# radioslave_v3.net
KiCad netlist of a schematic drawn in Altium Designer
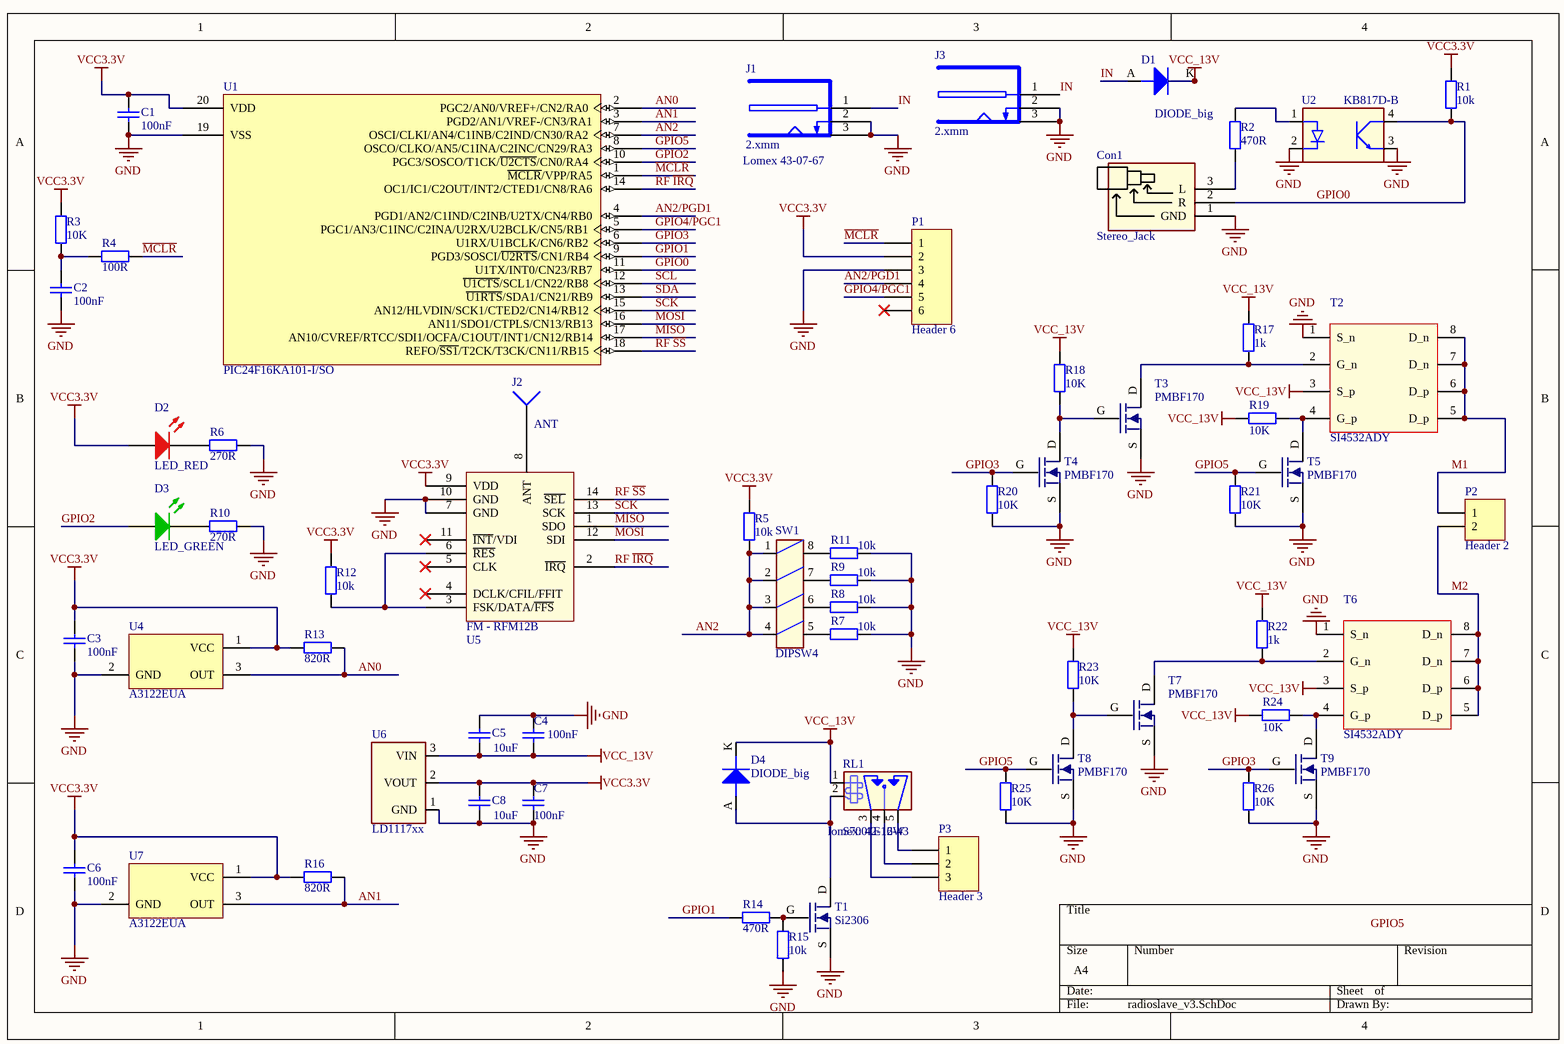
[diagram p0: radioslave_v3.SchDoc]

(export (version "E")
  (design (tool "Eeschema 10.0.6"))
  (components
    (comp (ref "C1")
      (value "100nF")
      (footprint "FP_0805_CAP_060")
      (description "Capacitor")
      (fields (field (name "PUBLISHER") "Altium Limited"))
      (libsource (lib "Miscellaneous Devices") (part "Cap"))
    )
    (comp (ref "C2")
      (value "100nF")
      (footprint "FP_0805_CAP_060")
      (description "Capacitor")
      (fields (field (name "PUBLISHER") "Altium Limited"))
      (libsource (lib "Miscellaneous Devices") (part "Cap"))
    )
    (comp (ref "C3")
      (value "100nF")
      (footprint "FP_0805_CAP_060")
      (description "Capacitor")
      (fields (field (name "PUBLISHER") "Altium Limited"))
      (libsource (lib "Miscellaneous Devices") (part "Cap"))
    )
    (comp (ref "C4")
      (value "100nF")
      (footprint "FP_0603_CAP_080")
      (description "Capacitor")
      (fields (field (name "PUBLISHER") "Altium Limited"))
      (libsource (lib "Miscellaneous Devices") (part "Cap"))
    )
    (comp (ref "C5")
      (value "10uF")
      (footprint "FP_1206_CAP_085")
      (description "Capacitor")
      (fields (field (name "PUBLISHER") "Altium Limited"))
      (libsource (lib "Miscellaneous Devices") (part "Cap"))
    )
    (comp (ref "C6")
      (value "100nF")
      (footprint "FP_0805_CAP_060")
      (description "Capacitor")
      (fields (field (name "PUBLISHER") "Altium Limited"))
      (libsource (lib "Miscellaneous Devices") (part "Cap"))
    )
    (comp (ref "C7")
      (value "100nF")
      (footprint "FP_0603_CAP_080")
      (description "Capacitor")
      (fields (field (name "PUBLISHER") "Altium Limited"))
      (libsource (lib "Miscellaneous Devices") (part "Cap"))
    )
    (comp (ref "C8")
      (value "10uF")
      (footprint "FP_1206_CAP_085")
      (description "Capacitor")
      (fields (field (name "PUBLISHER") "Altium Limited"))
      (libsource (lib "Miscellaneous Devices") (part "Cap"))
    )
    (comp (ref "Con1")
      (value "Stereo_Jack")
      (footprint "STEREO_JACK")
      (libsource (lib "Connector") (part "Stereo_Jack"))
    )
    (comp (ref "D1")
      (value "DIODE_big")
      (footprint "FP_SMA DO214AC")
      (libsource (lib "Diode") (part "DIODE_big"))
    )
    (comp (ref "D2")
      (value "LED_RED")
      (footprint "FP_0805_LED_RED")
      (description "Typical LED")
      (libsource (lib "Led_optical") (part "LED_R"))
    )
    (comp (ref "D3")
      (value "LED_GREEN")
      (footprint "FP_0805_LED_RED")
      (description "Typical LED")
      (libsource (lib "Led_optical") (part "LED_G"))
    )
    (comp (ref "D4")
      (value "DIODE_big")
      (footprint "FP_SMA DO214AC")
      (libsource (lib "Diode") (part "DIODE_big"))
    )
    (comp (ref "J1")
      (value "2.xmm")
      (footprint "FP_DC_TAP_ANYA")
      (description "2.xmm DC HEBA25 TÁPFESZÜLTSÉG ALJZAT ZÁRT, NYÁKBA 90°")
      (fields (field (name "ORDER INFO") "Lomex 43-07-67"))
      (libsource (lib "Connector") (part "DC_TAP_ANYA"))
    )
    (comp (ref "J2")
      (value "ANT")
      (footprint "PIN1")
      (description "Socket")
      (fields (field (name "PUBLISHER") "Altium Limited"))
      (libsource (lib "Miscellaneous Connectors") (part "Socket"))
    )
    (comp (ref "J3")
      (value "2.xmm")
      (footprint "FP_DC_TAP_ANYA")
      (description "2.xmm DC HEBA25 TÁPFESZÜLTSÉG ALJZAT ZÁRT, NYÁKBA 90°")
      (libsource (lib "Connector") (part "DC_TAP_ANYA"))
    )
    (comp (ref "P1")
      (value "Header 6")
      (footprint "HDR1X6")
      (description "Header, 6-Pin")
      (fields (field (name "PUBLISHER") "Altium Limited"))
      (libsource (lib "Miscellaneous Connectors") (part "Header 6"))
    )
    (comp (ref "P2")
      (value "Header 2")
      (footprint "HDR1X2")
      (description "Header, 2-Pin")
      (fields (field (name "PUBLISHER") "Altium Limited"))
      (libsource (lib "Miscellaneous Connectors") (part "Header 2"))
    )
    (comp (ref "P3")
      (value "Header 3")
      (footprint "SORKAPOCS 3 P RM3.81")
      (description "Header, 3-Pin")
      (fields (field (name "PUBLISHER") "Altium Limited"))
      (libsource (lib "Miscellaneous Connectors") (part "Header 3"))
    )
    (comp (ref "R1")
      (value "10k")
      (footprint "FP_0805_RES")
      (description "Resistor")
      (fields (field (name "PUBLISHER") "Altium Limited"))
      (libsource (lib "") (part "Res3_1"))
    )
    (comp (ref "R2")
      (value "470R")
      (footprint "FP_0805_RES")
      (description "Resistor")
      (fields (field (name "PUBLISHER") "Altium Limited"))
      (libsource (lib "") (part "Res3_1"))
    )
    (comp (ref "R3")
      (value "10K")
      (footprint "FP_0805_RES")
      (description "Resistor")
      (fields (field (name "PUBLISHER") "Altium Limited"))
      (libsource (lib "") (part "Res3_1"))
    )
    (comp (ref "R4")
      (value "100R")
      (footprint "FP_0805_RES")
      (description "Resistor")
      (fields (field (name "PUBLISHER") "Altium Limited"))
      (libsource (lib "Miscellaneous Devices") (part "Res3"))
    )
    (comp (ref "R5")
      (value "10k")
      (footprint "FP_0805_RES")
      (description "Resistor")
      (fields (field (name "PUBLISHER") "Altium Limited"))
      (libsource (lib "") (part "Res3_1"))
    )
    (comp (ref "R6")
      (value "270R")
      (footprint "FP_0805_RES")
      (description "Resistor")
      (fields (field (name "PUBLISHER") "Altium Limited"))
      (libsource (lib "Miscellaneous Devices") (part "Res3"))
    )
    (comp (ref "R7")
      (value "10k")
      (footprint "FP_0805_RES")
      (description "Resistor")
      (fields (field (name "PUBLISHER") "Altium Limited"))
      (libsource (lib "Miscellaneous Devices") (part "Res3"))
    )
    (comp (ref "R8")
      (value "10k")
      (footprint "FP_0805_RES")
      (description "Resistor")
      (fields (field (name "PUBLISHER") "Altium Limited"))
      (libsource (lib "Miscellaneous Devices") (part "Res3"))
    )
    (comp (ref "R9")
      (value "10k")
      (footprint "FP_0805_RES")
      (description "Resistor")
      (fields (field (name "PUBLISHER") "Altium Limited"))
      (libsource (lib "Miscellaneous Devices") (part "Res3"))
    )
    (comp (ref "R10")
      (value "270R")
      (footprint "FP_0805_RES")
      (description "Resistor")
      (fields (field (name "PUBLISHER") "Altium Limited"))
      (libsource (lib "Miscellaneous Devices") (part "Res3"))
    )
    (comp (ref "R11")
      (value "10k")
      (footprint "FP_0805_RES")
      (description "Resistor")
      (fields (field (name "PUBLISHER") "Altium Limited"))
      (libsource (lib "Miscellaneous Devices") (part "Res3"))
    )
    (comp (ref "R12")
      (value "10k")
      (footprint "FP_0805_RES")
      (description "Resistor")
      (fields (field (name "PUBLISHER") "Altium Limited"))
      (libsource (lib "") (part "Res3_2"))
    )
    (comp (ref "R13")
      (value "820R")
      (footprint "FP_0805_RES")
      (description "Resistor")
      (fields (field (name "PUBLISHER") "Altium Limited"))
      (libsource (lib "Miscellaneous Devices") (part "Res3"))
    )
    (comp (ref "R14")
      (value "470R")
      (footprint "FP_0805_RES")
      (description "Resistor")
      (fields (field (name "PUBLISHER") "Altium Limited"))
      (libsource (lib "Miscellaneous Devices") (part "Res3"))
    )
    (comp (ref "R15")
      (value "10k")
      (footprint "FP_0805_RES")
      (description "Resistor")
      (fields (field (name "PUBLISHER") "Altium Limited"))
      (libsource (lib "") (part "Res3_2"))
    )
    (comp (ref "R16")
      (value "820R")
      (footprint "FP_0805_RES")
      (description "Resistor")
      (fields (field (name "PUBLISHER") "Altium Limited"))
      (libsource (lib "Miscellaneous Devices") (part "Res3"))
    )
    (comp (ref "R17")
      (value "1k")
      (footprint "FP_0603_RES")
      (description "Resistor")
      (libsource (lib "") (part "Res3_1"))
    )
    (comp (ref "R18")
      (value "10K")
      (footprint "FP_0603_RES")
      (description "Resistor")
      (libsource (lib "") (part "RES_1"))
    )
    (comp (ref "R19")
      (value "10K")
      (footprint "FP_0603_RES")
      (description "Resistor")
      (libsource (lib "Resistor") (part "RES"))
    )
    (comp (ref "R20")
      (value "10K")
      (footprint "FP_0603_RES")
      (description "Resistor")
      (libsource (lib "") (part "RES_1"))
    )
    (comp (ref "R21")
      (value "10K")
      (footprint "FP_0603_RES")
      (description "Resistor")
      (libsource (lib "") (part "RES_1"))
    )
    (comp (ref "R22")
      (value "1k")
      (footprint "FP_0603_RES")
      (description "Resistor")
      (libsource (lib "") (part "Res3_1"))
    )
    (comp (ref "R23")
      (value "10K")
      (footprint "FP_0603_RES")
      (description "Resistor")
      (libsource (lib "") (part "RES_1"))
    )
    (comp (ref "R24")
      (value "10K")
      (footprint "FP_0603_RES")
      (description "Resistor")
      (libsource (lib "Resistor") (part "RES"))
    )
    (comp (ref "R25")
      (value "10K")
      (footprint "FP_0603_RES")
      (description "Resistor")
      (libsource (lib "") (part "RES_1"))
    )
    (comp (ref "R26")
      (value "10K")
      (footprint "FP_0603_RES")
      (description "Resistor")
      (libsource (lib "") (part "RES_1"))
    )
    (comp (ref "RL1")
      (value "S7001E12W")
      (footprint "RELAY_MORSE")
      (description "S7001E12W  12V morse 230AC/10A")
      (fields (field (name "ORDER INFO") "lomex: 42-16-43"))
      (libsource (lib "Switch") (part "RELAY_MORSE"))
    )
    (comp (ref "SW1")
      (value "DIPSW4")
      (footprint "DIP switch 4 TH")
      (libsource (lib "Switch") (part "DIPSW4"))
    )
    (comp (ref "T1") (value "Si2306") (footprint "FET_SOT23") (libsource (lib "FET") (part "NMOS")))
    (comp (ref "T2")
      (value "SI4532ADY")
      (footprint "FET_SOIC8_copper_pad")
      (libsource (lib "FET") (part "SI4532ADY   3.7A   30V"))
    )
    (comp (ref "T3") (value "PMBF170") (footprint "FET_SOT23") (libsource (lib "FET") (part "NMOS")))
    (comp (ref "T4") (value "PMBF170") (footprint "FET_SOT23") (libsource (lib "FET") (part "NMOS")))
    (comp (ref "T5") (value "PMBF170") (footprint "FET_SOT23") (libsource (lib "FET") (part "NMOS")))
    (comp (ref "T6")
      (value "SI4532ADY")
      (footprint "FET_SOIC8_copper_pad")
      (libsource (lib "FET") (part "SI4532ADY   3.7A   30V"))
    )
    (comp (ref "T7") (value "PMBF170") (footprint "FET_SOT23") (libsource (lib "FET") (part "NMOS")))
    (comp (ref "T8") (value "PMBF170") (footprint "FET_SOT23") (libsource (lib "FET") (part "NMOS")))
    (comp (ref "T9") (value "PMBF170") (footprint "FET_SOT23") (libsource (lib "FET") (part "NMOS")))
    (comp (ref "U1")
      (value "PIC24F16KA101-I/SO")
      (footprint "SOIC-SO20_N")
      (fields (field (name "PUBLISHER") "Altium Limited"))
      (libsource (lib "Microchip Microcontroller 16-Bit PIC24F") (part "PIC24F16KA101-I/SO"))
    )
    (comp (ref "U2")
      (value "KB817D-B")
      (footprint "SOP-4L")
      (description "KB817D-B (KIN) SOP-4L OPTOCOUPLER TRANS-OUT 300-600% 5kV SOP-4L [84-00-48]")
      (libsource (lib "Led_optical") (part "KB817D-B"))
    )
    (comp (ref "U4")
      (value "A3122EUA")
      (footprint "Allegro_hall sensor")
      (description "Hall-Effect Switch for High-Temperature Operation")
      (fields (field (name "PUBLISHER") "Altium Limited"))
      (libsource (lib "Sensor") (part "A3122EUA"))
    )
    (comp (ref "U5")
      (value "RFM12B")
      (footprint "RFM12B-S1")
      (description "FM Module")
      (libsource (lib "EtherIOv2") (part "RFM12B"))
    )
    (comp (ref "U6")
      (value "LD1117xx")
      (footprint "SUPPLY_SOT223")
      (description "LD1117xx 3,3V lin reg")
      (libsource (lib "Supply") (part "LD1117xx"))
    )
    (comp (ref "U7")
      (value "A3122EUA")
      (footprint "Allegro_hall sensor")
      (description "Hall-Effect Switch for High-Temperature Operation")
      (fields (field (name "PUBLISHER") "Altium Limited"))
      (libsource (lib "Sensor") (part "A3122EUA"))
    )
  )
  (nets
    (net (code "1") (name "/AN0") (class "Default")
      (node (ref "R13") (pin "1") (pinfunction "1_1") (pintype "passive"))
      (node (ref "U1") (pin "2") (pinfunction "PGC2/AN0/VREF+/CN2/RA0_2") (pintype "bidirectional"))
      (node (ref "U4") (pin "3") (pinfunction "OUT_3") (pintype "open_collector"))
    )
    (net (code "2") (name "/AN1") (class "Default")
      (node (ref "R16") (pin "1") (pinfunction "1_1") (pintype "passive"))
      (node (ref "U1") (pin "3") (pinfunction "PGD2/AN1/VREF-/CN3/RA1_3") (pintype "bidirectional"))
      (node (ref "U7") (pin "3") (pinfunction "OUT_3") (pintype "open_collector"))
    )
    (net (code "3") (name "/AN2") (class "Default")
      (node (ref "R5") (pin "2") (pinfunction "2_2") (pintype "passive"))
      (node (ref "SW1") (pin "1") (pinfunction "1_1") (pintype "passive"))
      (node (ref "SW1") (pin "2") (pinfunction "2_2") (pintype "passive"))
      (node (ref "SW1") (pin "3") (pinfunction "3_3") (pintype "passive"))
      (node (ref "SW1") (pin "4") (pinfunction "4_4") (pintype "passive"))
      (node (ref "U1") (pin "7") (pinfunction "OSCI/CLKI/AN4/C1INB/C2IND/CN30/RA2_7") (pintype "bidirectional"))
    )
    (net (code "4") (name "/AN2{slash}PGD1") (class "Default")
      (node (ref "P1") (pin "4") (pinfunction "4_4") (pintype "passive"))
      (node (ref "U1") (pin "4") (pinfunction "PGD1/AN2/C1IND/C2INB/U2TX/CN4/RB0_4") (pintype "bidirectional"))
    )
    (net (code "5") (name "/GPIO0") (class "Default")
      (node (ref "Con1") (pin "2") (pinfunction "R_2") (pintype "passive"))
      (node (ref "R1") (pin "2") (pinfunction "2_2") (pintype "passive"))
      (node (ref "U1") (pin "11") (pinfunction "U1TX/INT0/CN23/RB7_11") (pintype "bidirectional"))
      (node (ref "U2") (pin "4") (pinfunction "C_4") (pintype "passive"))
    )
    (net (code "6") (name "/GPIO1") (class "Default")
      (node (ref "R14") (pin "2") (pinfunction "2_2") (pintype "passive"))
      (node (ref "U1") (pin "9") (pinfunction "PGD3/SOSCI/~{U2RTS}/CN1/RB4_9") (pintype "bidirectional"))
    )
    (net (code "7") (name "/GPIO2") (class "Default")
      (node (ref "D3") (pin "A") (pinfunction "A_A") (pintype "passive"))
      (node (ref "U1") (pin "10") (pinfunction "PGC3/SOSCO/T1CK/~{U2CTS}/CN0/RA4_10") (pintype "bidirectional"))
    )
    (net (code "8") (name "/GPIO3") (class "Default")
      (node (ref "R20") (pin "2") (pinfunction "2_2") (pintype "passive"))
      (node (ref "R26") (pin "2") (pinfunction "2_2") (pintype "passive"))
      (node (ref "T4") (pin "G") (pinfunction "G_G") (pintype "passive"))
      (node (ref "T9") (pin "G") (pinfunction "G_G") (pintype "passive"))
      (node (ref "U1") (pin "6") (pinfunction "U1RX/U1BCLK/CN6/RB2_6") (pintype "bidirectional"))
    )
    (net (code "9") (name "/GPIO4{slash}PGC1") (class "Default")
      (node (ref "P1") (pin "5") (pinfunction "5_5") (pintype "passive"))
      (node (ref "U1") (pin "5") (pinfunction "PGC1/AN3/C1INC/C2INA/U2RX/U2BCLK/CN5/RB1_5") (pintype "bidirectional"))
    )
    (net (code "10") (name "/GPIO5") (class "Default")
      (node (ref "R21") (pin "2") (pinfunction "2_2") (pintype "passive"))
      (node (ref "R25") (pin "2") (pinfunction "2_2") (pintype "passive"))
      (node (ref "T5") (pin "G") (pinfunction "G_G") (pintype "passive"))
      (node (ref "T8") (pin "G") (pinfunction "G_G") (pintype "passive"))
      (node (ref "U1") (pin "8") (pinfunction "OSCO/CLKO/AN5/C1INA/C2INC/CN29/RA3_8") (pintype "bidirectional"))
    )
    (net (code "11") (name "/IN") (class "Default")
      (node (ref "D1") (pin "A") (pinfunction "A_A") (pintype "passive"))
      (node (ref "J1") (pin "1") (pinfunction "9V_1") (pintype "power_in"))
      (node (ref "J3") (pin "1") (pinfunction "9V_1") (pintype "power_in"))
    )
    (net (code "12") (name "/M1") (class "Default")
      (node (ref "P2") (pin "1") (pinfunction "1_1") (pintype "passive"))
      (node (ref "T2") (pin "5") (pinfunction "D_p_5") (pintype "passive"))
      (node (ref "T2") (pin "6") (pinfunction "D_p_6") (pintype "passive"))
      (node (ref "T2") (pin "7") (pinfunction "D_n_7") (pintype "passive"))
      (node (ref "T2") (pin "8") (pinfunction "D_n_8") (pintype "passive"))
    )
    (net (code "13") (name "/M2") (class "Default")
      (node (ref "P2") (pin "2") (pinfunction "2_2") (pintype "passive"))
      (node (ref "T6") (pin "5") (pinfunction "D_p_5") (pintype "passive"))
      (node (ref "T6") (pin "6") (pinfunction "D_p_6") (pintype "passive"))
      (node (ref "T6") (pin "7") (pinfunction "D_n_7") (pintype "passive"))
      (node (ref "T6") (pin "8") (pinfunction "D_n_8") (pintype "passive"))
    )
    (net (code "14") (name "/MISO") (class "Default")
      (node (ref "U1") (pin "17") (pinfunction "AN10/CVREF/RTCC/SDI1/OCFA/C1OUT/INT1/CN12/RB14_17") (pintype "bidirectional"))
      (node (ref "U5") (pin "1") (pinfunction "SDO_1") (pintype "passive"))
    )
    (net (code "15") (name "/MOSI") (class "Default")
      (node (ref "U1") (pin "16") (pinfunction "AN11/SDO1/CTPLS/CN13/RB13_16") (pintype "bidirectional"))
      (node (ref "U5") (pin "12") (pinfunction "SDI_12") (pintype "passive"))
    )
    (net (code "16") (name "/RF ~{IRQ}") (class "Default")
      (node (ref "U1") (pin "14") (pinfunction "OC1/IC1/C2OUT/INT2/CTED1/CN8/RA6_14") (pintype "bidirectional"))
      (node (ref "U5") (pin "2") (pinfunction "~{IRQ}_2") (pintype "passive"))
    )
    (net (code "17") (name "/RF ~{SS}") (class "Default")
      (node (ref "U1") (pin "18") (pinfunction "REFO/~{SS1}/T2CK/T3CK/CN11/RB15_18") (pintype "bidirectional"))
      (node (ref "U5") (pin "14") (pinfunction "~{SEL}_14") (pintype "passive"))
    )
    (net (code "18") (name "/SCK") (class "Default")
      (node (ref "U1") (pin "15") (pinfunction "AN12/HLVDIN/SCK1/CTED2/CN14/RB12_15") (pintype "bidirectional"))
      (node (ref "U5") (pin "13") (pinfunction "SCK_13") (pintype "passive"))
    )
    (net (code "19") (name "/SCL") (class "Default")
      (node (ref "U1") (pin "12") (pinfunction "~{U1CTS}/SCL1/CN22/RB8_12") (pintype "bidirectional"))
    )
    (net (code "20") (name "/SDA") (class "Default")
      (node (ref "U1") (pin "13") (pinfunction "~{U1RTS}/SDA1/CN21/RB9_13") (pintype "bidirectional"))
    )
    (net (code "21") (name "/~{MCLR}") (class "Default")
      (node (ref "P1") (pin "1") (pinfunction "1_1") (pintype "passive"))
      (node (ref "R4") (pin "1") (pinfunction "1_1") (pintype "passive"))
      (node (ref "U1") (pin "1") (pinfunction "~{MCLR}/VPP/RA5_1") (pintype "bidirectional"))
    )
    (net (code "22") (name "GND") (class "Default")
      (node (ref "C1") (pin "1") (pinfunction "1_1") (pintype "passive"))
      (node (ref "C2") (pin "1") (pinfunction "1_1") (pintype "passive"))
      (node (ref "C3") (pin "1") (pinfunction "1_1") (pintype "passive"))
      (node (ref "C4") (pin "1") (pinfunction "1_1") (pintype "passive"))
      (node (ref "C5") (pin "2") (pinfunction "2_2") (pintype "passive"))
      (node (ref "C6") (pin "1") (pinfunction "1_1") (pintype "passive"))
      (node (ref "C7") (pin "2") (pinfunction "2_2") (pintype "passive"))
      (node (ref "C8") (pin "1") (pinfunction "1_1") (pintype "passive"))
      (node (ref "Con1") (pin "1") (pinfunction "GND_1") (pintype "passive"))
      (node (ref "J1") (pin "2") (pinfunction "GND_2") (pintype "power_in"))
      (node (ref "J1") (pin "3") (pinfunction "GND_3") (pintype "power_in"))
      (node (ref "J3") (pin "2") (pinfunction "GND_2") (pintype "power_in"))
      (node (ref "J3") (pin "3") (pinfunction "GND_3") (pintype "power_in"))
      (node (ref "P1") (pin "3") (pinfunction "3_3") (pintype "passive"))
      (node (ref "R10") (pin "1") (pinfunction "1_1") (pintype "passive"))
      (node (ref "R11") (pin "1") (pinfunction "1_1") (pintype "passive"))
      (node (ref "R15") (pin "1") (pinfunction "1_1") (pintype "passive"))
      (node (ref "R20") (pin "1") (pinfunction "1_1") (pintype "passive"))
      (node (ref "R21") (pin "1") (pinfunction "1_1") (pintype "passive"))
      (node (ref "R25") (pin "1") (pinfunction "1_1") (pintype "passive"))
      (node (ref "R26") (pin "1") (pinfunction "1_1") (pintype "passive"))
      (node (ref "R6") (pin "1") (pinfunction "1_1") (pintype "passive"))
      (node (ref "R7") (pin "1") (pinfunction "1_1") (pintype "passive"))
      (node (ref "R8") (pin "1") (pinfunction "1_1") (pintype "passive"))
      (node (ref "R9") (pin "1") (pinfunction "1_1") (pintype "passive"))
      (node (ref "T1") (pin "S") (pinfunction "S_S") (pintype "passive"))
      (node (ref "T2") (pin "1") (pinfunction "S_n_1") (pintype "passive"))
      (node (ref "T3") (pin "S") (pinfunction "S_S") (pintype "passive"))
      (node (ref "T4") (pin "S") (pinfunction "S_S") (pintype "passive"))
      (node (ref "T5") (pin "S") (pinfunction "S_S") (pintype "passive"))
      (node (ref "T6") (pin "1") (pinfunction "S_n_1") (pintype "passive"))
      (node (ref "T7") (pin "S") (pinfunction "S_S") (pintype "passive"))
      (node (ref "T8") (pin "S") (pinfunction "S_S") (pintype "passive"))
      (node (ref "T9") (pin "S") (pinfunction "S_S") (pintype "passive"))
      (node (ref "U1") (pin "19") (pinfunction "VSS_19") (pintype "power_in"))
      (node (ref "U2") (pin "2") (pinfunction "K_2") (pintype "passive"))
      (node (ref "U2") (pin "3") (pinfunction "E_3") (pintype "passive"))
      (node (ref "U4") (pin "2") (pinfunction "GND_2") (pintype "power_in"))
      (node (ref "U5") (pin "10") (pinfunction "GND_10") (pintype "passive"))
      (node (ref "U5") (pin "7") (pinfunction "GND_7") (pintype "passive"))
      (node (ref "U6") (pin "1") (pinfunction "GND_1") (pintype "passive"))
      (node (ref "U7") (pin "2") (pinfunction "GND_2") (pintype "power_in"))
    )
    (net (code "23") (name "Net-(C2-Pad2)") (class "Default")
      (node (ref "C2") (pin "2") (pinfunction "2_2") (pintype "passive"))
      (node (ref "R3") (pin "2") (pinfunction "2_2") (pintype "passive"))
      (node (ref "R4") (pin "2") (pinfunction "2_2") (pintype "passive"))
    )
    (net (code "24") (name "Net-(Con1-L)") (class "Default")
      (node (ref "Con1") (pin "3") (pinfunction "L_3") (pintype "passive"))
      (node (ref "R2") (pin "2") (pinfunction "2_2") (pintype "passive"))
    )
    (net (code "25") (name "Net-(D2-PadK)") (class "Default")
      (node (ref "D2") (pin "K") (pinfunction "K_K") (pintype "passive"))
      (node (ref "R6") (pin "2") (pinfunction "2_2") (pintype "passive"))
    )
    (net (code "26") (name "Net-(D3-PadK)") (class "Default")
      (node (ref "D3") (pin "K") (pinfunction "K_K") (pintype "passive"))
      (node (ref "R10") (pin "2") (pinfunction "2_2") (pintype "passive"))
    )
    (net (code "27") (name "Net-(R7-Pad2)") (class "Default")
      (node (ref "R7") (pin "2") (pinfunction "2_2") (pintype "passive"))
      (node (ref "SW1") (pin "5") (pinfunction "5_5") (pintype "passive"))
    )
    (net (code "28") (name "Net-(R8-Pad2)") (class "Default")
      (node (ref "R8") (pin "2") (pinfunction "2_2") (pintype "passive"))
      (node (ref "SW1") (pin "6") (pinfunction "6_6") (pintype "passive"))
    )
    (net (code "29") (name "Net-(R9-Pad2)") (class "Default")
      (node (ref "R9") (pin "2") (pinfunction "2_2") (pintype "passive"))
      (node (ref "SW1") (pin "7") (pinfunction "7_7") (pintype "passive"))
    )
    (net (code "30") (name "Net-(R11-Pad2)") (class "Default")
      (node (ref "R11") (pin "2") (pinfunction "2_2") (pintype "passive"))
      (node (ref "SW1") (pin "8") (pinfunction "8_8") (pintype "passive"))
    )
    (net (code "31") (name "Net-(R14-Pad1)") (class "Default")
      (node (ref "R14") (pin "1") (pinfunction "1_1") (pintype "passive"))
      (node (ref "R15") (pin "2") (pinfunction "2_2") (pintype "passive"))
      (node (ref "T1") (pin "G") (pinfunction "G_G") (pintype "passive"))
    )
    (net (code "32") (name "Net-(R18-Pad1)") (class "Default")
      (node (ref "R18") (pin "1") (pinfunction "1_1") (pintype "passive"))
      (node (ref "T3") (pin "G") (pinfunction "G_G") (pintype "passive"))
      (node (ref "T4") (pin "D") (pinfunction "D_D") (pintype "passive"))
    )
    (net (code "33") (name "Net-(R23-Pad1)") (class "Default")
      (node (ref "R23") (pin "1") (pinfunction "1_1") (pintype "passive"))
      (node (ref "T7") (pin "G") (pinfunction "G_G") (pintype "passive"))
      (node (ref "T8") (pin "D") (pinfunction "D_D") (pintype "passive"))
    )
    (net (code "34") (name "Net-(RL1-COIL2+)") (class "Default")
      (node (ref "D4") (pin "A") (pinfunction "A_A") (pintype "passive"))
      (node (ref "RL1") (pin "2") (pinfunction "COIL2+_2") (pintype "passive"))
      (node (ref "T1") (pin "D") (pinfunction "D_D") (pintype "passive"))
    )
    (net (code "35") (name "Net-(RL1-COMMON)") (class "Default")
      (node (ref "P3") (pin "2") (pinfunction "2_2") (pintype "passive"))
      (node (ref "RL1") (pin "4") (pinfunction "COMMON_4") (pintype "passive"))
    )
    (net (code "36") (name "Net-(RL1-NC)") (class "Default")
      (node (ref "P3") (pin "3") (pinfunction "3_3") (pintype "passive"))
      (node (ref "RL1") (pin "3") (pinfunction "NC_3") (pintype "passive"))
    )
    (net (code "37") (name "Net-(RL1-NO)") (class "Default")
      (node (ref "P3") (pin "1") (pinfunction "1_1") (pintype "passive"))
      (node (ref "RL1") (pin "5") (pinfunction "NO_5") (pintype "passive"))
    )
    (net (code "38") (name "Net-(T2-G_n)") (class "Default")
      (node (ref "R17") (pin "2") (pinfunction "2_2") (pintype "passive"))
      (node (ref "T2") (pin "2") (pinfunction "G_n_2") (pintype "passive"))
      (node (ref "T3") (pin "D") (pinfunction "D_D") (pintype "passive"))
    )
    (net (code "39") (name "Net-(T2-G_p)") (class "Default")
      (node (ref "R19") (pin "2") (pinfunction "2_2") (pintype "passive"))
      (node (ref "T2") (pin "4") (pinfunction "G_p_4") (pintype "passive"))
      (node (ref "T5") (pin "D") (pinfunction "D_D") (pintype "passive"))
    )
    (net (code "40") (name "Net-(T6-G_n)") (class "Default")
      (node (ref "R22") (pin "2") (pinfunction "2_2") (pintype "passive"))
      (node (ref "T6") (pin "2") (pinfunction "G_n_2") (pintype "passive"))
      (node (ref "T7") (pin "D") (pinfunction "D_D") (pintype "passive"))
    )
    (net (code "41") (name "Net-(T6-G_p)") (class "Default")
      (node (ref "R24") (pin "2") (pinfunction "2_2") (pintype "passive"))
      (node (ref "T6") (pin "4") (pinfunction "G_p_4") (pintype "passive"))
      (node (ref "T9") (pin "D") (pinfunction "D_D") (pintype "passive"))
    )
    (net (code "42") (name "Net-(U2-A)") (class "Default")
      (node (ref "R2") (pin "1") (pinfunction "1_1") (pintype "passive"))
      (node (ref "U2") (pin "1") (pinfunction "A_1") (pintype "passive"))
    )
    (net (code "43") (name "Net-(U5-ANT)") (class "Default")
      (node (ref "J2") (pin "1") (pinfunction "1_1") (pintype "passive"))
      (node (ref "U5") (pin "8") (pinfunction "ANT_8") (pintype "passive"))
    )
    (net (code "44") (name "Net-(U5-FSK{slash}DATA{slash}~{FFS})") (class "Default")
      (node (ref "R12") (pin "1") (pinfunction "1_1") (pintype "passive"))
      (node (ref "U5") (pin "3") (pinfunction "FSK/DATA/~{FFS}_3") (pintype "passive"))
      (node (ref "U5") (pin "6") (pinfunction "~{RES}_6") (pintype "passive"))
    )
    (net (code "45") (name "VCC3.3V") (class "Default")
      (node (ref "C1") (pin "2") (pinfunction "2_2") (pintype "passive"))
      (node (ref "C3") (pin "2") (pinfunction "2_2") (pintype "passive"))
      (node (ref "C6") (pin "2") (pinfunction "2_2") (pintype "passive"))
      (node (ref "C7") (pin "1") (pinfunction "1_1") (pintype "passive"))
      (node (ref "C8") (pin "2") (pinfunction "2_2") (pintype "passive"))
      (node (ref "D2") (pin "A") (pinfunction "A_A") (pintype "passive"))
      (node (ref "P1") (pin "2") (pinfunction "2_2") (pintype "passive"))
      (node (ref "R1") (pin "1") (pinfunction "1_1") (pintype "passive"))
      (node (ref "R12") (pin "2") (pinfunction "2_2") (pintype "passive"))
      (node (ref "R13") (pin "2") (pinfunction "2_2") (pintype "passive"))
      (node (ref "R16") (pin "2") (pinfunction "2_2") (pintype "passive"))
      (node (ref "R3") (pin "1") (pinfunction "1_1") (pintype "passive"))
      (node (ref "R5") (pin "1") (pinfunction "1_1") (pintype "passive"))
      (node (ref "U1") (pin "20") (pinfunction "VDD_20") (pintype "power_in"))
      (node (ref "U4") (pin "1") (pinfunction "VCC_1") (pintype "power_in"))
      (node (ref "U5") (pin "9") (pinfunction "VDD_9") (pintype "passive"))
      (node (ref "U6") (pin "2") (pinfunction "VOUT_2") (pintype "passive"))
      (node (ref "U7") (pin "1") (pinfunction "VCC_1") (pintype "power_in"))
    )
    (net (code "46") (name "VCC_13V") (class "Default")
      (node (ref "C4") (pin "2") (pinfunction "2_2") (pintype "passive"))
      (node (ref "C5") (pin "1") (pinfunction "1_1") (pintype "passive"))
      (node (ref "D1") (pin "K") (pinfunction "K_K") (pintype "passive"))
      (node (ref "D4") (pin "K") (pinfunction "K_K") (pintype "passive"))
      (node (ref "R17") (pin "1") (pinfunction "1_1") (pintype "passive"))
      (node (ref "R18") (pin "2") (pinfunction "2_2") (pintype "passive"))
      (node (ref "R19") (pin "1") (pinfunction "1_1") (pintype "passive"))
      (node (ref "R22") (pin "1") (pinfunction "1_1") (pintype "passive"))
      (node (ref "R23") (pin "2") (pinfunction "2_2") (pintype "passive"))
      (node (ref "R24") (pin "1") (pinfunction "1_1") (pintype "passive"))
      (node (ref "RL1") (pin "1") (pinfunction "COIL1-_1") (pintype "passive"))
      (node (ref "T2") (pin "3") (pinfunction "S_p_3") (pintype "passive"))
      (node (ref "T6") (pin "3") (pinfunction "S_p_3") (pintype "passive"))
      (node (ref "U6") (pin "3") (pinfunction "VIN_3") (pintype "passive"))
    )
    (net (code "47") (name "unconnected-(P1-Pad6)") (class "Default")
      (node (ref "P1") (pin "6") (pinfunction "6_6") (pintype "passive+no_connect"))
    )
    (net (code "48") (name "unconnected-(U5-CLK-Pad5)") (class "Default")
      (node (ref "U5") (pin "5") (pinfunction "CLK_5") (pintype "passive+no_connect"))
    )
    (net (code "49") (name "unconnected-(U5-DCLK{slash}CFIL{slash}FFIT-Pad4)") (class "Default")
      (node (ref "U5") (pin "4") (pinfunction "DCLK/CFIL/FFIT_4") (pintype "passive+no_connect"))
    )
    (net (code "50") (name "unconnected-(U5-~{INT}{slash}VDI-Pad11)") (class "Default")
      (node (ref "U5") (pin "11") (pinfunction "~{INT}/VDI_11") (pintype "passive+no_connect"))
    )
  )
)
